# ShieldLed.net
KiCad netlist of a schematic drawn in EAGLE
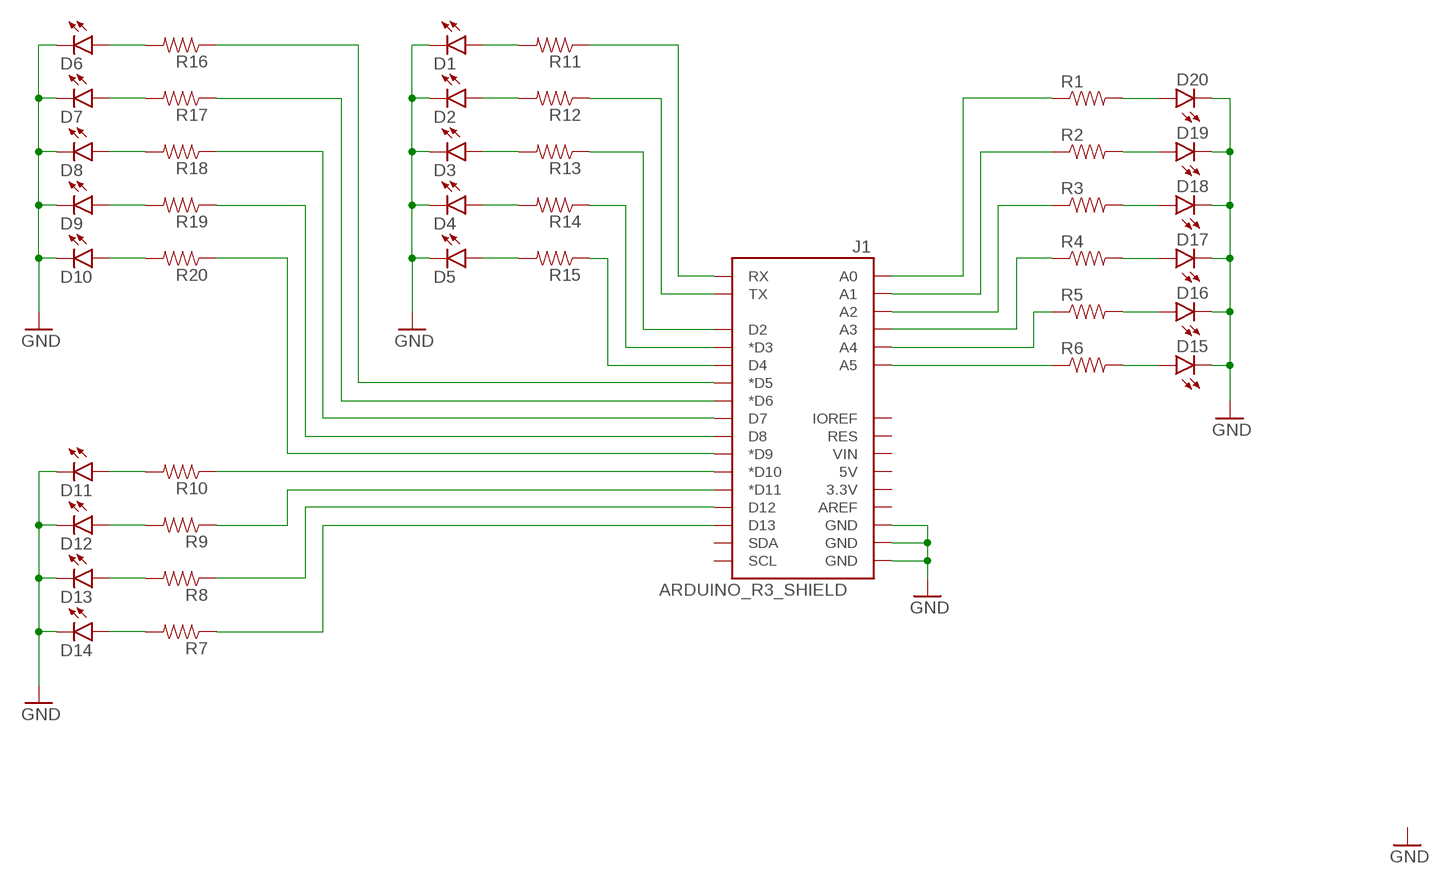
[diagram p0: schematic, sheet 1]

(export (version "E")
  (design (tool "Eeschema 10.0.6"))
  (components
    (comp (ref "D1")
      (value "LED1206")
      (footprint "eagle-import:LED-1206")
      (libsource (lib "eagle-import") (part "LED1206"))
    )
    (comp (ref "D2")
      (value "LED1206")
      (footprint "eagle-import:LED-1206")
      (libsource (lib "eagle-import") (part "LED1206"))
    )
    (comp (ref "D3")
      (value "LED1206")
      (footprint "eagle-import:LED-1206")
      (libsource (lib "eagle-import") (part "LED1206"))
    )
    (comp (ref "D4")
      (value "LED1206")
      (footprint "eagle-import:LED-1206")
      (libsource (lib "eagle-import") (part "LED1206"))
    )
    (comp (ref "D5")
      (value "LED1206")
      (footprint "eagle-import:LED-1206")
      (libsource (lib "eagle-import") (part "LED1206"))
    )
    (comp (ref "D6")
      (value "LED1206")
      (footprint "eagle-import:LED-1206")
      (libsource (lib "eagle-import") (part "LED1206"))
    )
    (comp (ref "D7")
      (value "LED1206")
      (footprint "eagle-import:LED-1206")
      (libsource (lib "eagle-import") (part "LED1206"))
    )
    (comp (ref "D8")
      (value "LED1206")
      (footprint "eagle-import:LED-1206")
      (libsource (lib "eagle-import") (part "LED1206"))
    )
    (comp (ref "D9")
      (value "LED1206")
      (footprint "eagle-import:LED-1206")
      (libsource (lib "eagle-import") (part "LED1206"))
    )
    (comp (ref "D10")
      (value "LED1206")
      (footprint "eagle-import:LED-1206")
      (libsource (lib "eagle-import") (part "LED1206"))
    )
    (comp (ref "D11")
      (value "LED1206")
      (footprint "eagle-import:LED-1206")
      (libsource (lib "eagle-import") (part "LED1206"))
    )
    (comp (ref "D12")
      (value "LED1206")
      (footprint "eagle-import:LED-1206")
      (libsource (lib "eagle-import") (part "LED1206"))
    )
    (comp (ref "D13")
      (value "LED1206")
      (footprint "eagle-import:LED-1206")
      (libsource (lib "eagle-import") (part "LED1206"))
    )
    (comp (ref "D14")
      (value "LED1206")
      (footprint "eagle-import:LED-1206")
      (libsource (lib "eagle-import") (part "LED1206"))
    )
    (comp (ref "D15")
      (value "LED1206")
      (footprint "eagle-import:LED-1206")
      (libsource (lib "eagle-import") (part "LED1206"))
    )
    (comp (ref "D16")
      (value "LED1206")
      (footprint "eagle-import:LED-1206")
      (libsource (lib "eagle-import") (part "LED1206"))
    )
    (comp (ref "D17")
      (value "LED1206")
      (footprint "eagle-import:LED-1206")
      (libsource (lib "eagle-import") (part "LED1206"))
    )
    (comp (ref "D18")
      (value "LED1206")
      (footprint "eagle-import:LED-1206")
      (libsource (lib "eagle-import") (part "LED1206"))
    )
    (comp (ref "D19")
      (value "LED1206")
      (footprint "eagle-import:LED-1206")
      (libsource (lib "eagle-import") (part "LED1206"))
    )
    (comp (ref "D20")
      (value "LED1206")
      (footprint "eagle-import:LED-1206")
      (libsource (lib "eagle-import") (part "LED1206"))
    )
    (comp (ref "J1")
      (value "ARDUINO_R3_SHIELD")
      (footprint "eagle-import:UNO_R3_SHIELD")
      (libsource (lib "eagle-import") (part "ARDUINO_R3_SHIELD"))
    )
    (comp (ref "R1")
      (value "RESISTOR1206")
      (footprint "eagle-import:1206")
      (libsource (lib "eagle-import") (part "RESISTOR1206"))
    )
    (comp (ref "R2")
      (value "RESISTOR1206")
      (footprint "eagle-import:1206")
      (libsource (lib "eagle-import") (part "RESISTOR1206"))
    )
    (comp (ref "R3")
      (value "RESISTOR1206")
      (footprint "eagle-import:1206")
      (libsource (lib "eagle-import") (part "RESISTOR1206"))
    )
    (comp (ref "R4")
      (value "RESISTOR1206")
      (footprint "eagle-import:1206")
      (libsource (lib "eagle-import") (part "RESISTOR1206"))
    )
    (comp (ref "R5")
      (value "RESISTOR1206")
      (footprint "eagle-import:1206")
      (libsource (lib "eagle-import") (part "RESISTOR1206"))
    )
    (comp (ref "R6")
      (value "RESISTOR1206")
      (footprint "eagle-import:1206")
      (libsource (lib "eagle-import") (part "RESISTOR1206"))
    )
    (comp (ref "R7")
      (value "RESISTOR1206")
      (footprint "eagle-import:1206")
      (libsource (lib "eagle-import") (part "RESISTOR1206"))
    )
    (comp (ref "R8")
      (value "RESISTOR1206")
      (footprint "eagle-import:1206")
      (libsource (lib "eagle-import") (part "RESISTOR1206"))
    )
    (comp (ref "R9")
      (value "RESISTOR1206")
      (footprint "eagle-import:1206")
      (libsource (lib "eagle-import") (part "RESISTOR1206"))
    )
    (comp (ref "R10")
      (value "RESISTOR1206")
      (footprint "eagle-import:1206")
      (libsource (lib "eagle-import") (part "RESISTOR1206"))
    )
    (comp (ref "R11")
      (value "RESISTOR1206")
      (footprint "eagle-import:1206")
      (libsource (lib "eagle-import") (part "RESISTOR1206"))
    )
    (comp (ref "R12")
      (value "RESISTOR1206")
      (footprint "eagle-import:1206")
      (libsource (lib "eagle-import") (part "RESISTOR1206"))
    )
    (comp (ref "R13")
      (value "RESISTOR1206")
      (footprint "eagle-import:1206")
      (libsource (lib "eagle-import") (part "RESISTOR1206"))
    )
    (comp (ref "R14")
      (value "RESISTOR1206")
      (footprint "eagle-import:1206")
      (libsource (lib "eagle-import") (part "RESISTOR1206"))
    )
    (comp (ref "R15")
      (value "RESISTOR1206")
      (footprint "eagle-import:1206")
      (libsource (lib "eagle-import") (part "RESISTOR1206"))
    )
    (comp (ref "R16")
      (value "RESISTOR1206")
      (footprint "eagle-import:1206")
      (libsource (lib "eagle-import") (part "RESISTOR1206"))
    )
    (comp (ref "R17")
      (value "RESISTOR1206")
      (footprint "eagle-import:1206")
      (libsource (lib "eagle-import") (part "RESISTOR1206"))
    )
    (comp (ref "R18")
      (value "RESISTOR1206")
      (footprint "eagle-import:1206")
      (libsource (lib "eagle-import") (part "RESISTOR1206"))
    )
    (comp (ref "R19")
      (value "RESISTOR1206")
      (footprint "eagle-import:1206")
      (libsource (lib "eagle-import") (part "RESISTOR1206"))
    )
    (comp (ref "R20")
      (value "RESISTOR1206")
      (footprint "eagle-import:1206")
      (libsource (lib "eagle-import") (part "RESISTOR1206"))
    )
  )
  (nets
    (net (code "1") (name "GND") (class "Default")
      (node (ref "D1") (pin "C") (pinfunction "C_C") (pintype "passive"))
      (node (ref "D10") (pin "C") (pinfunction "C_C") (pintype "passive"))
      (node (ref "D11") (pin "C") (pinfunction "C_C") (pintype "passive"))
      (node (ref "D12") (pin "C") (pinfunction "C_C") (pintype "passive"))
      (node (ref "D13") (pin "C") (pinfunction "C_C") (pintype "passive"))
      (node (ref "D14") (pin "C") (pinfunction "C_C") (pintype "passive"))
      (node (ref "D15") (pin "C") (pinfunction "C_C") (pintype "passive"))
      (node (ref "D16") (pin "C") (pinfunction "C_C") (pintype "passive"))
      (node (ref "D17") (pin "C") (pinfunction "C_C") (pintype "passive"))
      (node (ref "D18") (pin "C") (pinfunction "C_C") (pintype "passive"))
      (node (ref "D19") (pin "C") (pinfunction "C_C") (pintype "passive"))
      (node (ref "D2") (pin "C") (pinfunction "C_C") (pintype "passive"))
      (node (ref "D20") (pin "C") (pinfunction "C_C") (pintype "passive"))
      (node (ref "D3") (pin "C") (pinfunction "C_C") (pintype "passive"))
      (node (ref "D4") (pin "C") (pinfunction "C_C") (pintype "passive"))
      (node (ref "D5") (pin "C") (pinfunction "C_C") (pintype "passive"))
      (node (ref "D6") (pin "C") (pinfunction "C_C") (pintype "passive"))
      (node (ref "D7") (pin "C") (pinfunction "C_C") (pintype "passive"))
      (node (ref "D8") (pin "C") (pinfunction "C_C") (pintype "passive"))
      (node (ref "D9") (pin "C") (pinfunction "C_C") (pintype "passive"))
      (node (ref "J1") (pin "GND@0") (pinfunction "GND_GND@0") (pintype "bidirectional"))
      (node (ref "J1") (pin "GND@1") (pinfunction "GND_GND@1") (pintype "bidirectional"))
      (node (ref "J1") (pin "GND@2") (pinfunction "GND_GND@2") (pintype "bidirectional"))
    )
    (net (code "2") (name "Net-(D1-PadA)") (class "Default")
      (node (ref "D1") (pin "A") (pinfunction "A_A") (pintype "passive"))
      (node (ref "R11") (pin "2") (pinfunction "2_2") (pintype "passive"))
    )
    (net (code "3") (name "Net-(D2-PadA)") (class "Default")
      (node (ref "D2") (pin "A") (pinfunction "A_A") (pintype "passive"))
      (node (ref "R12") (pin "2") (pinfunction "2_2") (pintype "passive"))
    )
    (net (code "4") (name "Net-(D3-PadA)") (class "Default")
      (node (ref "D3") (pin "A") (pinfunction "A_A") (pintype "passive"))
      (node (ref "R13") (pin "2") (pinfunction "2_2") (pintype "passive"))
    )
    (net (code "5") (name "Net-(D4-PadA)") (class "Default")
      (node (ref "D4") (pin "A") (pinfunction "A_A") (pintype "passive"))
      (node (ref "R14") (pin "2") (pinfunction "2_2") (pintype "passive"))
    )
    (net (code "6") (name "Net-(D5-PadA)") (class "Default")
      (node (ref "D5") (pin "A") (pinfunction "A_A") (pintype "passive"))
      (node (ref "R15") (pin "2") (pinfunction "2_2") (pintype "passive"))
    )
    (net (code "7") (name "Net-(D6-PadA)") (class "Default")
      (node (ref "D6") (pin "A") (pinfunction "A_A") (pintype "passive"))
      (node (ref "R16") (pin "2") (pinfunction "2_2") (pintype "passive"))
    )
    (net (code "8") (name "Net-(D7-PadA)") (class "Default")
      (node (ref "D7") (pin "A") (pinfunction "A_A") (pintype "passive"))
      (node (ref "R17") (pin "2") (pinfunction "2_2") (pintype "passive"))
    )
    (net (code "9") (name "Net-(D8-PadA)") (class "Default")
      (node (ref "D8") (pin "A") (pinfunction "A_A") (pintype "passive"))
      (node (ref "R18") (pin "2") (pinfunction "2_2") (pintype "passive"))
    )
    (net (code "10") (name "Net-(D9-PadA)") (class "Default")
      (node (ref "D9") (pin "A") (pinfunction "A_A") (pintype "passive"))
      (node (ref "R19") (pin "2") (pinfunction "2_2") (pintype "passive"))
    )
    (net (code "11") (name "Net-(D10-PadA)") (class "Default")
      (node (ref "D10") (pin "A") (pinfunction "A_A") (pintype "passive"))
      (node (ref "R20") (pin "2") (pinfunction "2_2") (pintype "passive"))
    )
    (net (code "12") (name "Net-(D11-PadA)") (class "Default")
      (node (ref "D11") (pin "A") (pinfunction "A_A") (pintype "passive"))
      (node (ref "R10") (pin "2") (pinfunction "2_2") (pintype "passive"))
    )
    (net (code "13") (name "Net-(D12-PadA)") (class "Default")
      (node (ref "D12") (pin "A") (pinfunction "A_A") (pintype "passive"))
      (node (ref "R9") (pin "2") (pinfunction "2_2") (pintype "passive"))
    )
    (net (code "14") (name "Net-(D13-PadA)") (class "Default")
      (node (ref "D13") (pin "A") (pinfunction "A_A") (pintype "passive"))
      (node (ref "R8") (pin "2") (pinfunction "2_2") (pintype "passive"))
    )
    (net (code "15") (name "Net-(D14-PadA)") (class "Default")
      (node (ref "D14") (pin "A") (pinfunction "A_A") (pintype "passive"))
      (node (ref "R7") (pin "2") (pinfunction "2_2") (pintype "passive"))
    )
    (net (code "16") (name "Net-(D15-PadA)") (class "Default")
      (node (ref "D15") (pin "A") (pinfunction "A_A") (pintype "passive"))
      (node (ref "R6") (pin "2") (pinfunction "2_2") (pintype "passive"))
    )
    (net (code "17") (name "Net-(D16-PadA)") (class "Default")
      (node (ref "D16") (pin "A") (pinfunction "A_A") (pintype "passive"))
      (node (ref "R5") (pin "2") (pinfunction "2_2") (pintype "passive"))
    )
    (net (code "18") (name "Net-(D17-PadA)") (class "Default")
      (node (ref "D17") (pin "A") (pinfunction "A_A") (pintype "passive"))
      (node (ref "R4") (pin "2") (pinfunction "2_2") (pintype "passive"))
    )
    (net (code "19") (name "Net-(D18-PadA)") (class "Default")
      (node (ref "D18") (pin "A") (pinfunction "A_A") (pintype "passive"))
      (node (ref "R3") (pin "2") (pinfunction "2_2") (pintype "passive"))
    )
    (net (code "20") (name "Net-(D19-PadA)") (class "Default")
      (node (ref "D19") (pin "A") (pinfunction "A_A") (pintype "passive"))
      (node (ref "R2") (pin "2") (pinfunction "2_2") (pintype "passive"))
    )
    (net (code "21") (name "Net-(D20-PadA)") (class "Default")
      (node (ref "D20") (pin "A") (pinfunction "A_A") (pintype "passive"))
      (node (ref "R1") (pin "2") (pinfunction "2_2") (pintype "passive"))
    )
    (net (code "22") (name "Net-(J1-*D3)") (class "Default")
      (node (ref "J1") (pin "D3") (pinfunction "*D3_D3") (pintype "bidirectional"))
      (node (ref "R14") (pin "1") (pinfunction "1_1") (pintype "passive"))
    )
    (net (code "23") (name "Net-(J1-*D5)") (class "Default")
      (node (ref "J1") (pin "D5") (pinfunction "*D5_D5") (pintype "bidirectional"))
      (node (ref "R16") (pin "1") (pinfunction "1_1") (pintype "passive"))
    )
    (net (code "24") (name "Net-(J1-*D6)") (class "Default")
      (node (ref "J1") (pin "D6") (pinfunction "*D6_D6") (pintype "bidirectional"))
      (node (ref "R17") (pin "1") (pinfunction "1_1") (pintype "passive"))
    )
    (net (code "25") (name "Net-(J1-*D9)") (class "Default")
      (node (ref "J1") (pin "D9") (pinfunction "*D9_D9") (pintype "bidirectional"))
      (node (ref "R20") (pin "1") (pinfunction "1_1") (pintype "passive"))
    )
    (net (code "26") (name "Net-(J1-*D10)") (class "Default")
      (node (ref "J1") (pin "D10") (pinfunction "*D10_D10") (pintype "bidirectional"))
      (node (ref "R10") (pin "1") (pinfunction "1_1") (pintype "passive"))
    )
    (net (code "27") (name "Net-(J1-*D11)") (class "Default")
      (node (ref "J1") (pin "D11") (pinfunction "*D11_D11") (pintype "bidirectional"))
      (node (ref "R9") (pin "1") (pinfunction "1_1") (pintype "passive"))
    )
    (net (code "28") (name "Net-(J1-PadA0)") (class "Default")
      (node (ref "J1") (pin "A0") (pinfunction "A0_A0") (pintype "bidirectional"))
      (node (ref "R1") (pin "1") (pinfunction "1_1") (pintype "passive"))
    )
    (net (code "29") (name "Net-(J1-PadA1)") (class "Default")
      (node (ref "J1") (pin "A1") (pinfunction "A1_A1") (pintype "bidirectional"))
      (node (ref "R2") (pin "1") (pinfunction "1_1") (pintype "passive"))
    )
    (net (code "30") (name "Net-(J1-PadA2)") (class "Default")
      (node (ref "J1") (pin "A2") (pinfunction "A2_A2") (pintype "bidirectional"))
      (node (ref "R3") (pin "1") (pinfunction "1_1") (pintype "passive"))
    )
    (net (code "31") (name "Net-(J1-PadA3)") (class "Default")
      (node (ref "J1") (pin "A3") (pinfunction "A3_A3") (pintype "bidirectional"))
      (node (ref "R4") (pin "1") (pinfunction "1_1") (pintype "passive"))
    )
    (net (code "32") (name "Net-(J1-PadA4)") (class "Default")
      (node (ref "J1") (pin "A4") (pinfunction "A4_A4") (pintype "bidirectional"))
      (node (ref "R5") (pin "1") (pinfunction "1_1") (pintype "passive"))
    )
    (net (code "33") (name "Net-(J1-PadA5)") (class "Default")
      (node (ref "J1") (pin "A5") (pinfunction "A5_A5") (pintype "bidirectional"))
      (node (ref "R6") (pin "1") (pinfunction "1_1") (pintype "passive"))
    )
    (net (code "34") (name "Net-(J1-PadD2)") (class "Default")
      (node (ref "J1") (pin "D2") (pinfunction "D2_D2") (pintype "bidirectional"))
      (node (ref "R13") (pin "1") (pinfunction "1_1") (pintype "passive"))
    )
    (net (code "35") (name "Net-(J1-PadD4)") (class "Default")
      (node (ref "J1") (pin "D4") (pinfunction "D4_D4") (pintype "bidirectional"))
      (node (ref "R15") (pin "1") (pinfunction "1_1") (pintype "passive"))
    )
    (net (code "36") (name "Net-(J1-PadD7)") (class "Default")
      (node (ref "J1") (pin "D7") (pinfunction "D7_D7") (pintype "bidirectional"))
      (node (ref "R18") (pin "1") (pinfunction "1_1") (pintype "passive"))
    )
    (net (code "37") (name "Net-(J1-PadD8)") (class "Default")
      (node (ref "J1") (pin "D8") (pinfunction "D8_D8") (pintype "bidirectional"))
      (node (ref "R19") (pin "1") (pinfunction "1_1") (pintype "passive"))
    )
    (net (code "38") (name "Net-(J1-PadD12)") (class "Default")
      (node (ref "J1") (pin "D12") (pinfunction "D12_D12") (pintype "bidirectional"))
      (node (ref "R8") (pin "1") (pinfunction "1_1") (pintype "passive"))
    )
    (net (code "39") (name "Net-(J1-PadD13)") (class "Default")
      (node (ref "J1") (pin "D13") (pinfunction "D13_D13") (pintype "bidirectional"))
      (node (ref "R7") (pin "1") (pinfunction "1_1") (pintype "passive"))
    )
    (net (code "40") (name "Net-(J1-PadRX)") (class "Default")
      (node (ref "J1") (pin "RX") (pinfunction "RX_RX") (pintype "bidirectional"))
      (node (ref "R11") (pin "1") (pinfunction "1_1") (pintype "passive"))
    )
    (net (code "41") (name "Net-(J1-PadTX)") (class "Default")
      (node (ref "J1") (pin "TX") (pinfunction "TX_TX") (pintype "bidirectional"))
      (node (ref "R12") (pin "1") (pinfunction "1_1") (pintype "passive"))
    )
    (net (code "42") (name "unconnected-(J1-Pad3.3V)") (class "Default")
      (node (ref "J1") (pin "3.3V") (pinfunction "3.3V_3.3V") (pintype "bidirectional"))
    )
    (net (code "43") (name "unconnected-(J1-Pad5V)") (class "Default")
      (node (ref "J1") (pin "5V") (pinfunction "5V_5V") (pintype "bidirectional"))
    )
    (net (code "44") (name "unconnected-(J1-PadAREF)") (class "Default")
      (node (ref "J1") (pin "AREF") (pinfunction "AREF_AREF") (pintype "bidirectional"))
    )
    (net (code "45") (name "unconnected-(J1-PadIOREF)") (class "Default")
      (node (ref "J1") (pin "IOREF") (pinfunction "IOREF_IOREF") (pintype "bidirectional"))
    )
    (net (code "46") (name "unconnected-(J1-PadRES)") (class "Default")
      (node (ref "J1") (pin "RES") (pinfunction "RES_RES") (pintype "bidirectional"))
    )
    (net (code "47") (name "unconnected-(J1-PadSCL)") (class "Default")
      (node (ref "J1") (pin "SCL") (pinfunction "SCL_SCL") (pintype "bidirectional"))
    )
    (net (code "48") (name "unconnected-(J1-PadSDA)") (class "Default")
      (node (ref "J1") (pin "SDA") (pinfunction "SDA_SDA") (pintype "bidirectional"))
    )
    (net (code "49") (name "unconnected-(J1-PadVIN)") (class "Default")
      (node (ref "J1") (pin "VIN") (pinfunction "VIN_VIN") (pintype "bidirectional"))
    )
  )
)
